# emg.net
KiCad netlist of a schematic drawn in EAGLE
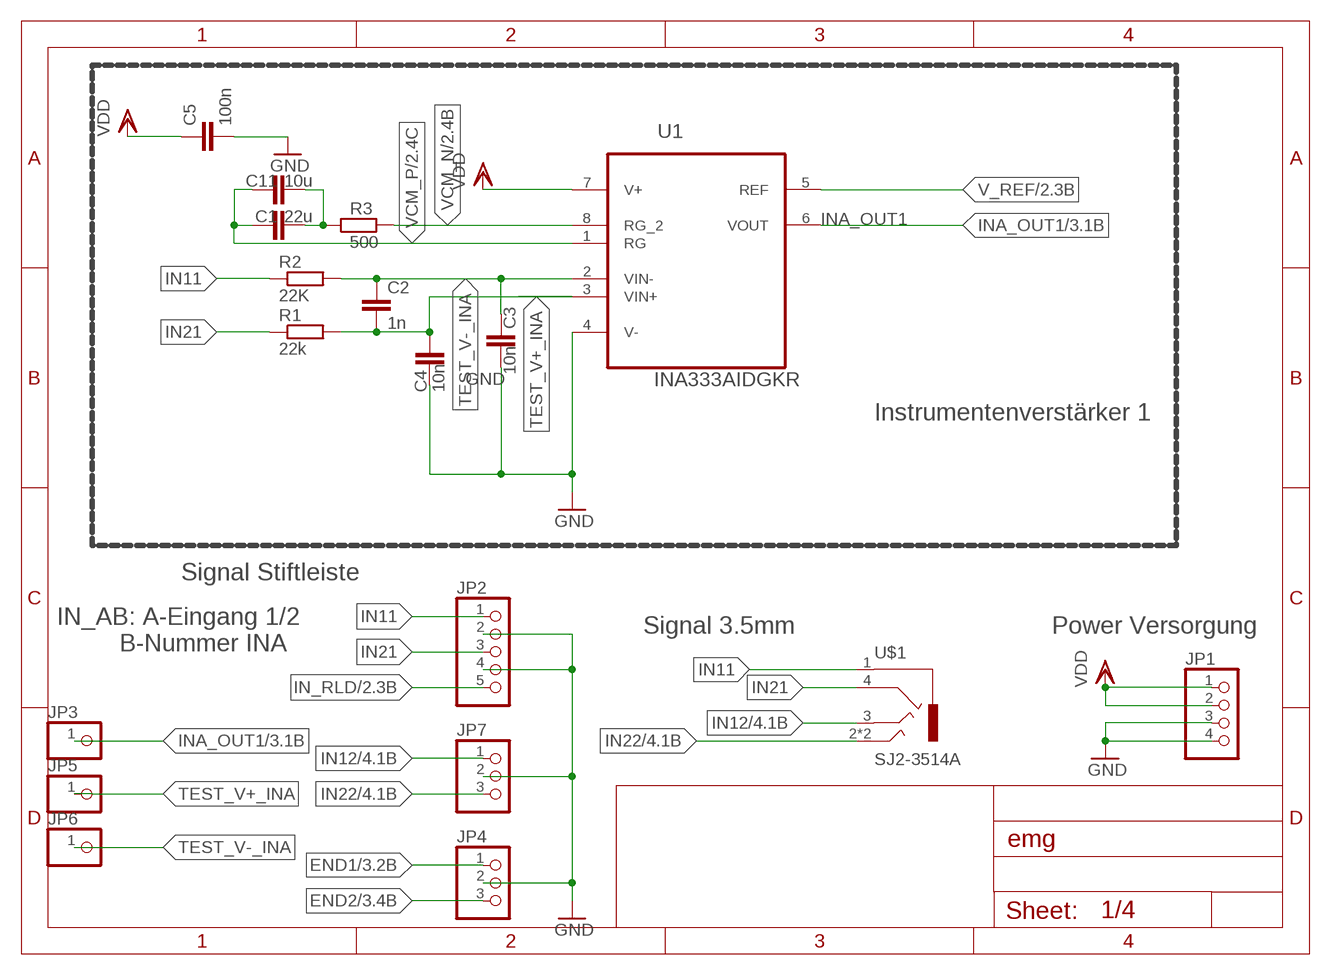
[diagram p0: schematic, sheet 1]
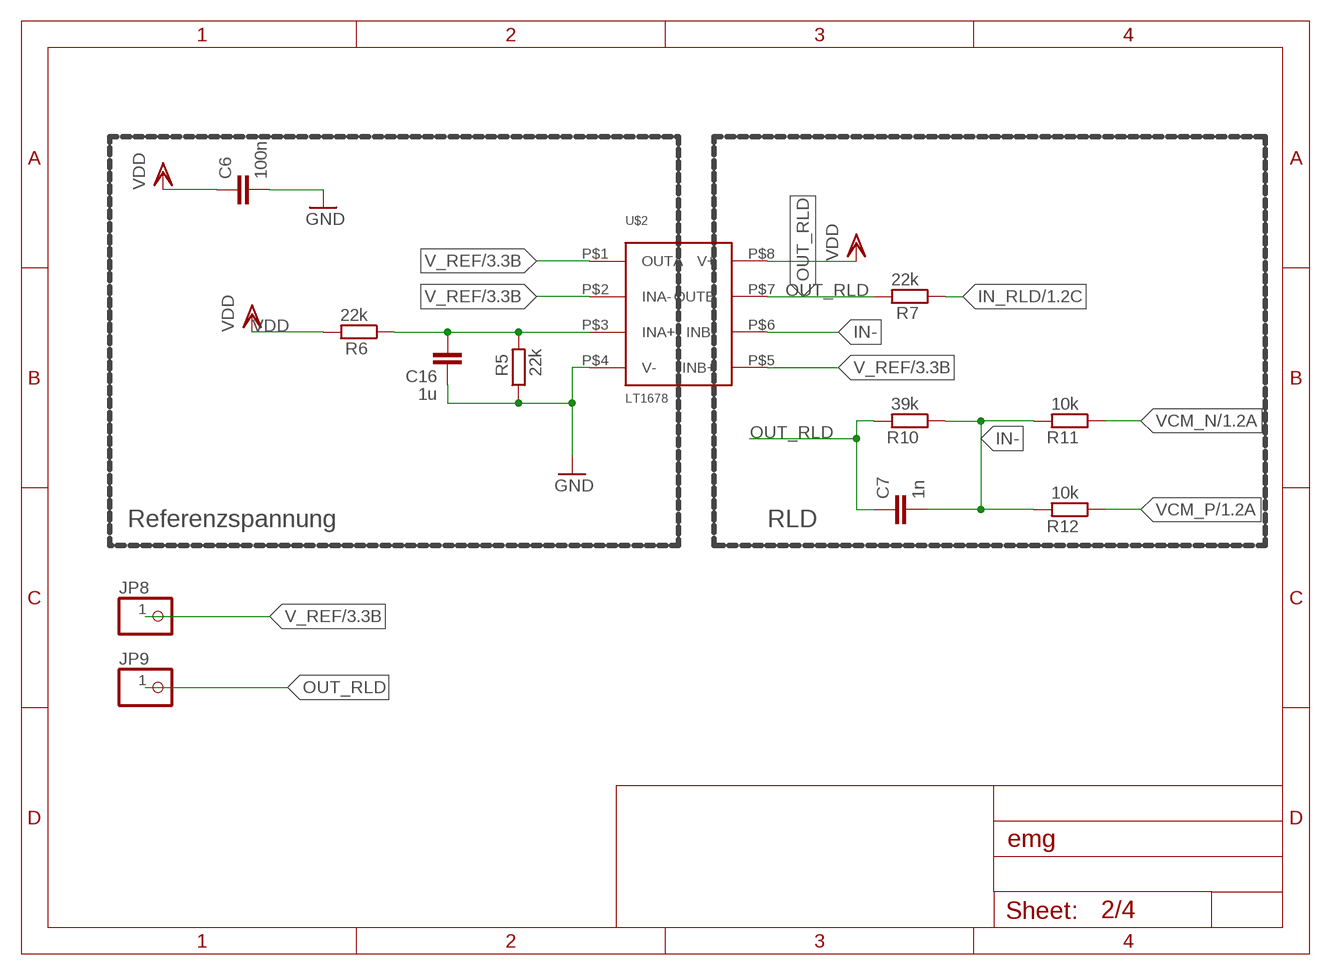
[diagram p1: schematic, sheet 2]
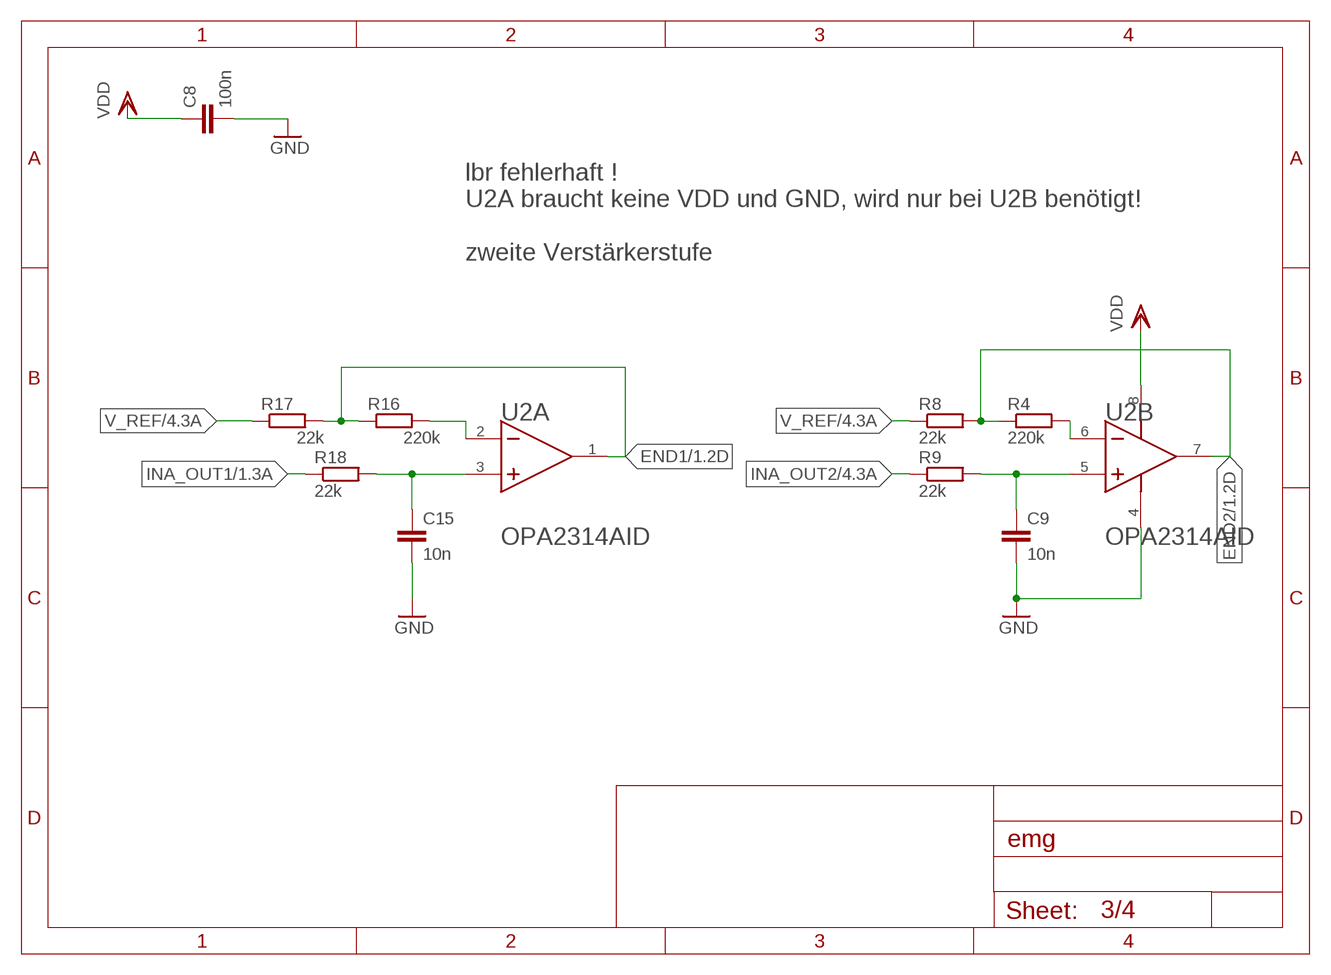
[diagram p2: schematic, sheet 3]
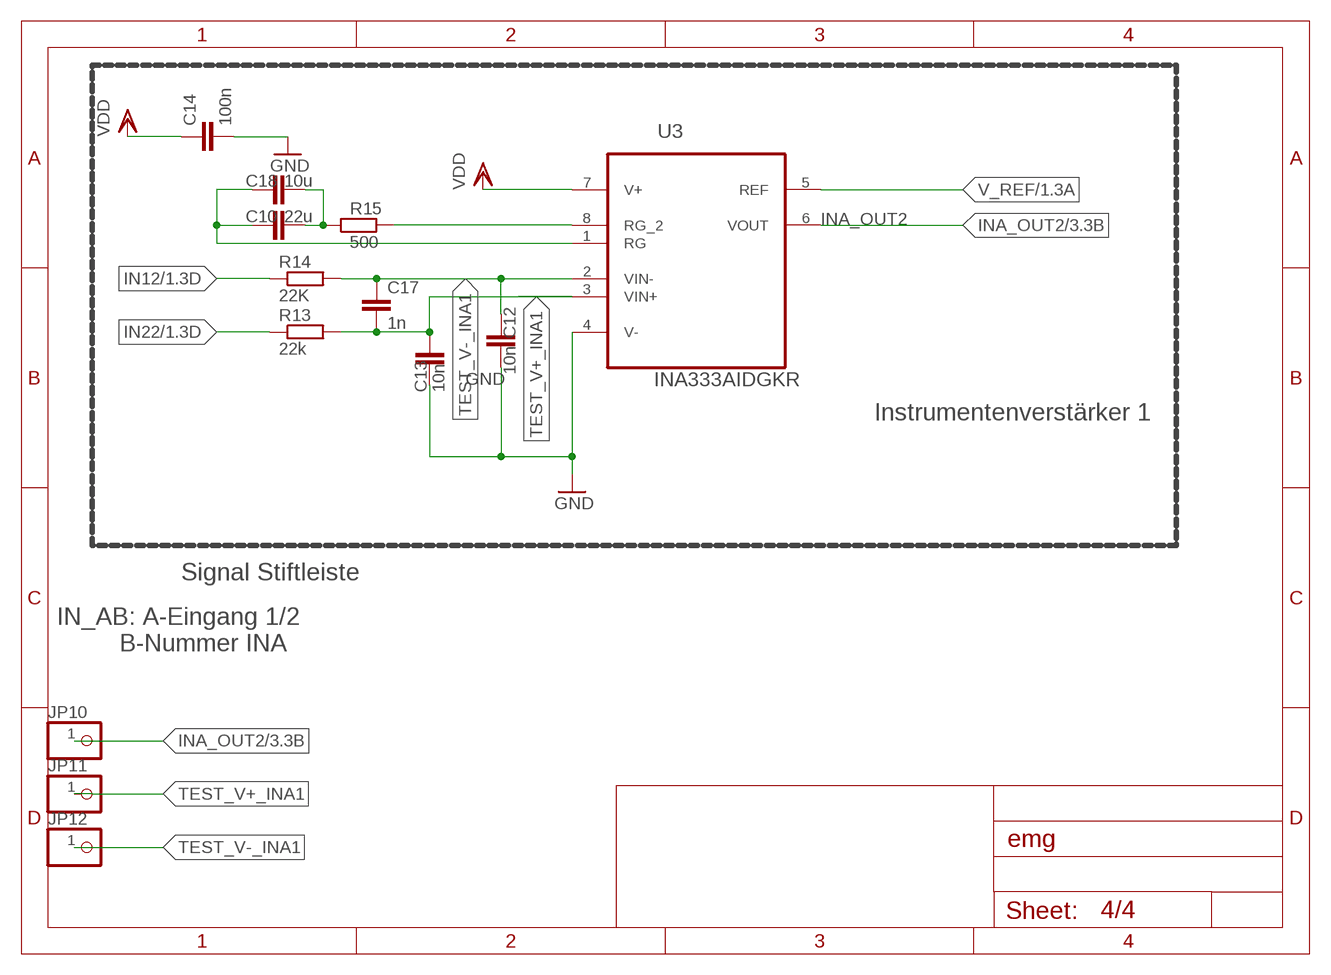
[diagram p3: schematic, sheet 4]

(export (version "E")
  (design (tool "Eeschema 10.0.6"))
  (components
    (comp (ref "C6")
      (value "100n")
      (footprint "eagle-import:C0805")
      (libsource (lib "eagle-import") (part "C-EUC0805"))
    )
    (comp (ref "C7")
      (value "1n")
      (footprint "eagle-import:C0805")
      (libsource (lib "eagle-import") (part "C-EUC0805"))
    )
    (comp (ref "C16")
      (value "1u")
      (footprint "eagle-import:C0805")
      (libsource (lib "eagle-import") (part "C-EUC0805"))
    )
    (comp (ref "JP8")
      (value "PINHD-1X1")
      (footprint "eagle-import:1X01")
      (libsource (lib "eagle-import") (part "PINHD-1X1"))
    )
    (comp (ref "JP9")
      (value "PINHD-1X1")
      (footprint "eagle-import:1X01")
      (libsource (lib "eagle-import") (part "PINHD-1X1"))
    )
    (comp (ref "R5")
      (value "22k")
      (footprint "eagle-import:R0805")
      (libsource (lib "eagle-import") (part "R-EU_R0805"))
    )
    (comp (ref "R6")
      (value "22k")
      (footprint "eagle-import:R0805")
      (libsource (lib "eagle-import") (part "R-EU_R0805"))
    )
    (comp (ref "R7")
      (value "22k")
      (footprint "eagle-import:R0805")
      (libsource (lib "eagle-import") (part "R-EU_R0805"))
    )
    (comp (ref "R10")
      (value "39k")
      (footprint "eagle-import:R0805")
      (libsource (lib "eagle-import") (part "R-EU_R0805"))
    )
    (comp (ref "R11")
      (value "10k")
      (footprint "eagle-import:R0805")
      (libsource (lib "eagle-import") (part "R-EU_R0805"))
    )
    (comp (ref "R12")
      (value "10k")
      (footprint "eagle-import:R0805")
      (libsource (lib "eagle-import") (part "R-EU_R0805"))
    )
    (comp (ref "U$2")
      (value "LT1678")
      (footprint "eagle-import:S8")
      (libsource (lib "eagle-import") (part "LT1678"))
    )
    (comp (ref "C8")
      (value "100n")
      (footprint "eagle-import:C0805")
      (libsource (lib "eagle-import") (part "C-EUC0805"))
    )
    (comp (ref "C9")
      (value "10n")
      (footprint "eagle-import:C0805")
      (libsource (lib "eagle-import") (part "C-EUC0805"))
    )
    (comp (ref "C15")
      (value "10n")
      (footprint "eagle-import:C0805")
      (libsource (lib "eagle-import") (part "C-EUC0805"))
    )
    (comp (ref "R4")
      (value "220k")
      (footprint "eagle-import:R0805")
      (libsource (lib "eagle-import") (part "R-EU_R0805"))
    )
    (comp (ref "R8")
      (value "22k")
      (footprint "eagle-import:R0805")
      (libsource (lib "eagle-import") (part "R-EU_R0805"))
    )
    (comp (ref "R9")
      (value "22k")
      (footprint "eagle-import:R0805")
      (libsource (lib "eagle-import") (part "R-EU_R0805"))
    )
    (comp (ref "R16")
      (value "220k")
      (footprint "eagle-import:R0805")
      (libsource (lib "eagle-import") (part "R-EU_R0805"))
    )
    (comp (ref "R17")
      (value "22k")
      (footprint "eagle-import:R0805")
      (libsource (lib "eagle-import") (part "R-EU_R0805"))
    )
    (comp (ref "R18")
      (value "22k")
      (footprint "eagle-import:R0805")
      (libsource (lib "eagle-import") (part "R-EU_R0805"))
    )
    (comp (ref "U2")
      (value "TEXAS_INSTRUMENTS_OPA2314AIDTEXAS_INSTRUMENTS_OPA2314AID_0_0")
      (footprint "eagle-import:TEXAS_INSTRUMENTS_OPA2314AID_0")
      (fields (field (name "MF") "Texas Instruments") (field (name "MPN") "OPA2314AID"))
      (libsource (lib "eagle-import") (part "TEXAS_INSTRUMENTS_OPA2314AIDTEXAS_INSTRUMENTS_OPA2314AID_0_0"))
    )
    (comp (ref "C10")
      (value "22u")
      (footprint "eagle-import:C0805")
      (libsource (lib "eagle-import") (part "C-EUC0805"))
    )
    (comp (ref "C12")
      (value "10n")
      (footprint "eagle-import:C0805")
      (libsource (lib "eagle-import") (part "C-EUC0805"))
    )
    (comp (ref "C13")
      (value "10n")
      (footprint "eagle-import:C0805")
      (libsource (lib "eagle-import") (part "C-EUC0805"))
    )
    (comp (ref "C14")
      (value "100n")
      (footprint "eagle-import:C0805")
      (libsource (lib "eagle-import") (part "C-EUC0805"))
    )
    (comp (ref "C17")
      (value "1n")
      (footprint "eagle-import:C0805")
      (libsource (lib "eagle-import") (part "C-EUC0805"))
    )
    (comp (ref "C18")
      (value "10u")
      (footprint "eagle-import:C0805")
      (libsource (lib "eagle-import") (part "C-EUC0805"))
    )
    (comp (ref "JP10")
      (value "PINHD-1X1")
      (footprint "eagle-import:1X01")
      (libsource (lib "eagle-import") (part "PINHD-1X1"))
    )
    (comp (ref "JP11")
      (value "PINHD-1X1")
      (footprint "eagle-import:1X01")
      (libsource (lib "eagle-import") (part "PINHD-1X1"))
    )
    (comp (ref "JP12")
      (value "PINHD-1X1")
      (footprint "eagle-import:1X01")
      (libsource (lib "eagle-import") (part "PINHD-1X1"))
    )
    (comp (ref "R13")
      (value "22k")
      (footprint "eagle-import:R0805")
      (libsource (lib "eagle-import") (part "R-EU_R0805"))
    )
    (comp (ref "R14")
      (value "22K")
      (footprint "eagle-import:R0805")
      (libsource (lib "eagle-import") (part "R-EU_R0805"))
    )
    (comp (ref "R15")
      (value "500")
      (footprint "eagle-import:R0805")
      (libsource (lib "eagle-import") (part "R-EU_R0805"))
    )
    (comp (ref "U3")
      (value "INA333AIDGKR")
      (footprint "eagle-import:SOP65P490X110-8N")
      (libsource (lib "eagle-import") (part "INA333AIDGKR"))
    )
    (comp (ref "C1")
      (value "22u")
      (footprint "eagle-import:C0805")
      (libsource (lib "eagle-import") (part "C-EUC0805"))
    )
    (comp (ref "C2")
      (value "1n")
      (footprint "eagle-import:C0805")
      (libsource (lib "eagle-import") (part "C-EUC0805"))
    )
    (comp (ref "C3")
      (value "10n")
      (footprint "eagle-import:C0805")
      (libsource (lib "eagle-import") (part "C-EUC0805"))
    )
    (comp (ref "C4")
      (value "10n")
      (footprint "eagle-import:C0805")
      (libsource (lib "eagle-import") (part "C-EUC0805"))
    )
    (comp (ref "C5")
      (value "100n")
      (footprint "eagle-import:C0805")
      (libsource (lib "eagle-import") (part "C-EUC0805"))
    )
    (comp (ref "C11")
      (value "10u")
      (footprint "eagle-import:C0805")
      (libsource (lib "eagle-import") (part "C-EUC0805"))
    )
    (comp (ref "JP1")
      (value "PINHD-1X4")
      (footprint "eagle-import:1X04")
      (libsource (lib "eagle-import") (part "PINHD-1X4"))
    )
    (comp (ref "JP2")
      (value "PINHD-1X5")
      (footprint "eagle-import:1X05")
      (libsource (lib "eagle-import") (part "PINHD-1X5"))
    )
    (comp (ref "JP3")
      (value "PINHD-1X1")
      (footprint "eagle-import:1X01")
      (libsource (lib "eagle-import") (part "PINHD-1X1"))
    )
    (comp (ref "JP4")
      (value "PINHD-1X3")
      (footprint "eagle-import:1X03")
      (libsource (lib "eagle-import") (part "PINHD-1X3"))
    )
    (comp (ref "JP5")
      (value "PINHD-1X1")
      (footprint "eagle-import:1X01")
      (libsource (lib "eagle-import") (part "PINHD-1X1"))
    )
    (comp (ref "JP6")
      (value "PINHD-1X1")
      (footprint "eagle-import:1X01")
      (libsource (lib "eagle-import") (part "PINHD-1X1"))
    )
    (comp (ref "JP7")
      (value "PINHD-1X3")
      (footprint "eagle-import:1X03")
      (libsource (lib "eagle-import") (part "PINHD-1X3"))
    )
    (comp (ref "R1")
      (value "22k")
      (footprint "eagle-import:R0805")
      (libsource (lib "eagle-import") (part "R-EU_R0805"))
    )
    (comp (ref "R2")
      (value "22K")
      (footprint "eagle-import:R0805")
      (libsource (lib "eagle-import") (part "R-EU_R0805"))
    )
    (comp (ref "R3")
      (value "500")
      (footprint "eagle-import:R0805")
      (libsource (lib "eagle-import") (part "R-EU_R0805"))
    )
    (comp (ref "U$1")
      (value "SJ2-3514A")
      (footprint "eagle-import:USR_SJ2-4514A")
      (libsource (lib "eagle-import") (part "SJ2-3514A"))
    )
    (comp (ref "U1")
      (value "INA333AIDGKR")
      (footprint "eagle-import:SOP65P490X110-8N")
      (libsource (lib "eagle-import") (part "INA333AIDGKR"))
    )
  )
  (nets
    (net (code "1") (name "END1") (class "Default")
      (node (ref "JP4") (pin "1") (pinfunction "1_1") (pintype "passive"))
      (node (ref "R16") (pin "1") (pinfunction "1_1") (pintype "passive"))
      (node (ref "R17") (pin "2") (pinfunction "2_2") (pintype "passive"))
      (node (ref "U2") (pin "1") (pinfunction "OUT_A_1") (pintype "output"))
    )
    (net (code "2") (name "END2") (class "Default")
      (node (ref "JP4") (pin "3") (pinfunction "3_3") (pintype "passive"))
      (node (ref "R4") (pin "1") (pinfunction "1_1") (pintype "passive"))
      (node (ref "R8") (pin "2") (pinfunction "2_2") (pintype "passive"))
      (node (ref "U2") (pin "7") (pinfunction "OUT_B_7") (pintype "output"))
    )
    (net (code "3") (name "GND") (class "Default")
      (node (ref "C12") (pin "2") (pinfunction "2_2") (pintype "passive"))
      (node (ref "C13") (pin "2") (pinfunction "2_2") (pintype "passive"))
      (node (ref "C14") (pin "2") (pinfunction "2_2") (pintype "passive"))
      (node (ref "C15") (pin "2") (pinfunction "2_2") (pintype "passive"))
      (node (ref "C16") (pin "1") (pinfunction "1_1") (pintype "passive"))
      (node (ref "C3") (pin "2") (pinfunction "2_2") (pintype "passive"))
      (node (ref "C4") (pin "2") (pinfunction "2_2") (pintype "passive"))
      (node (ref "C5") (pin "2") (pinfunction "2_2") (pintype "passive"))
      (node (ref "C6") (pin "2") (pinfunction "2_2") (pintype "passive"))
      (node (ref "C8") (pin "2") (pinfunction "2_2") (pintype "passive"))
      (node (ref "C9") (pin "2") (pinfunction "2_2") (pintype "passive"))
      (node (ref "JP1") (pin "3") (pinfunction "3_3") (pintype "passive"))
      (node (ref "JP1") (pin "4") (pinfunction "4_4") (pintype "passive"))
      (node (ref "JP2") (pin "2") (pinfunction "2_2") (pintype "passive"))
      (node (ref "JP2") (pin "4") (pinfunction "4_4") (pintype "passive"))
      (node (ref "JP4") (pin "2") (pinfunction "2_2") (pintype "passive"))
      (node (ref "JP7") (pin "2") (pinfunction "2_2") (pintype "passive"))
      (node (ref "R5") (pin "1") (pinfunction "1_1") (pintype "passive"))
      (node (ref "U$2") (pin "P$4") (pinfunction "V-_P$4") (pintype "power_in"))
      (node (ref "U1") (pin "4") (pinfunction "V-_4") (pintype "power_in"))
      (node (ref "U2") (pin "4") (pinfunction "V-_4") (pintype "power_in"))
      (node (ref "U3") (pin "4") (pinfunction "V-_4") (pintype "power_in"))
    )
    (net (code "4") (name "IN-") (class "Default")
      (node (ref "C7") (pin "2") (pinfunction "2_2") (pintype "passive"))
      (node (ref "R10") (pin "1") (pinfunction "1_1") (pintype "passive"))
      (node (ref "R11") (pin "2") (pinfunction "2_2") (pintype "passive"))
      (node (ref "R12") (pin "2") (pinfunction "2_2") (pintype "passive"))
      (node (ref "U$2") (pin "P$6") (pinfunction "INB-_P$6") (pintype "input"))
    )
    (net (code "5") (name "IN11") (class "Default")
      (node (ref "JP2") (pin "1") (pinfunction "1_1") (pintype "passive"))
      (node (ref "R2") (pin "1") (pinfunction "1_1") (pintype "passive"))
      (node (ref "U$1") (pin "1") (pinfunction "1_1") (pintype "passive"))
    )
    (net (code "6") (name "IN12") (class "Default")
      (node (ref "JP7") (pin "1") (pinfunction "1_1") (pintype "passive"))
      (node (ref "R14") (pin "1") (pinfunction "1_1") (pintype "passive"))
      (node (ref "U$1") (pin "3") (pinfunction "3_3") (pintype "passive"))
    )
    (net (code "7") (name "IN21") (class "Default")
      (node (ref "JP2") (pin "3") (pinfunction "3_3") (pintype "passive"))
      (node (ref "R1") (pin "1") (pinfunction "1_1") (pintype "passive"))
      (node (ref "U$1") (pin "4") (pinfunction "4_4") (pintype "passive"))
    )
    (net (code "8") (name "IN22") (class "Default")
      (node (ref "JP7") (pin "3") (pinfunction "3_3") (pintype "passive"))
      (node (ref "R13") (pin "1") (pinfunction "1_1") (pintype "passive"))
      (node (ref "U$1") (pin "2") (pinfunction "2_2") (pintype "passive"))
      (node (ref "U$1") (pin "2_2") (pinfunction "2_2_2") (pintype "passive"))
    )
    (net (code "9") (name "INA_OUT1") (class "Default")
      (node (ref "JP3") (pin "1") (pinfunction "1_1") (pintype "passive"))
      (node (ref "R18") (pin "1") (pinfunction "1_1") (pintype "passive"))
      (node (ref "U1") (pin "6") (pinfunction "VOUT_6") (pintype "output"))
    )
    (net (code "10") (name "INA_OUT2") (class "Default")
      (node (ref "JP10") (pin "1") (pinfunction "1_1") (pintype "passive"))
      (node (ref "R9") (pin "1") (pinfunction "1_1") (pintype "passive"))
      (node (ref "U3") (pin "6") (pinfunction "VOUT_6") (pintype "output"))
    )
    (net (code "11") (name "IN_RLD") (class "Default")
      (node (ref "JP2") (pin "5") (pinfunction "5_5") (pintype "passive"))
      (node (ref "R7") (pin "1") (pinfunction "1_1") (pintype "passive"))
    )
    (net (code "12") (name "Net-(C1-Pad2)") (class "Default")
      (node (ref "C1") (pin "2") (pinfunction "2_2") (pintype "passive"))
      (node (ref "C11") (pin "2") (pinfunction "2_2") (pintype "passive"))
      (node (ref "R3") (pin "1") (pinfunction "1_1") (pintype "passive"))
    )
    (net (code "13") (name "Net-(C10-Pad2)") (class "Default")
      (node (ref "C10") (pin "2") (pinfunction "2_2") (pintype "passive"))
      (node (ref "C18") (pin "2") (pinfunction "2_2") (pintype "passive"))
      (node (ref "R15") (pin "1") (pinfunction "1_1") (pintype "passive"))
    )
    (net (code "14") (name "Net-(U$2-INA+)") (class "Default")
      (node (ref "C16") (pin "2") (pinfunction "2_2") (pintype "passive"))
      (node (ref "R5") (pin "2") (pinfunction "2_2") (pintype "passive"))
      (node (ref "R6") (pin "1") (pinfunction "1_1") (pintype "passive"))
      (node (ref "U$2") (pin "P$3") (pinfunction "INA+_P$3") (pintype "input"))
    )
    (net (code "15") (name "Net-(U2A-IN_A+)") (class "Default")
      (node (ref "C15") (pin "1") (pinfunction "1_1") (pintype "passive"))
      (node (ref "R18") (pin "2") (pinfunction "2_2") (pintype "passive"))
      (node (ref "U2") (pin "3") (pinfunction "IN_A+_3") (pintype "input"))
    )
    (net (code "16") (name "Net-(U2A-IN_A-)") (class "Default")
      (node (ref "R16") (pin "2") (pinfunction "2_2") (pintype "passive"))
      (node (ref "U2") (pin "2") (pinfunction "IN_A-_2") (pintype "input"))
    )
    (net (code "17") (name "Net-(U2B-IN_B+)") (class "Default")
      (node (ref "C9") (pin "1") (pinfunction "1_1") (pintype "passive"))
      (node (ref "R9") (pin "2") (pinfunction "2_2") (pintype "passive"))
      (node (ref "U2") (pin "5") (pinfunction "IN_B+_5") (pintype "input"))
    )
    (net (code "18") (name "Net-(U2B-IN_B-)") (class "Default")
      (node (ref "R4") (pin "2") (pinfunction "2_2") (pintype "passive"))
      (node (ref "U2") (pin "6") (pinfunction "IN_B-_6") (pintype "input"))
    )
    (net (code "19") (name "Net-(U3-RG)") (class "Default")
      (node (ref "C10") (pin "1") (pinfunction "1_1") (pintype "passive"))
      (node (ref "C18") (pin "1") (pinfunction "1_1") (pintype "passive"))
      (node (ref "U3") (pin "1") (pinfunction "RG_1") (pintype "input"))
    )
    (net (code "20") (name "Net-(U3-RG_2)") (class "Default")
      (node (ref "R15") (pin "2") (pinfunction "2_2") (pintype "passive"))
      (node (ref "U3") (pin "8") (pinfunction "RG_2_8") (pintype "input"))
    )
    (net (code "21") (name "OUT_RLD") (class "Default")
      (node (ref "C7") (pin "1") (pinfunction "1_1") (pintype "passive"))
      (node (ref "JP9") (pin "1") (pinfunction "1_1") (pintype "passive"))
      (node (ref "R10") (pin "2") (pinfunction "2_2") (pintype "passive"))
      (node (ref "R7") (pin "2") (pinfunction "2_2") (pintype "passive"))
      (node (ref "U$2") (pin "P$7") (pinfunction "OUTB_P$7") (pintype "output"))
    )
    (net (code "22") (name "TEST_V+_INA") (class "Default")
      (node (ref "C2") (pin "2") (pinfunction "2_2") (pintype "passive"))
      (node (ref "C4") (pin "1") (pinfunction "1_1") (pintype "passive"))
      (node (ref "JP5") (pin "1") (pinfunction "1_1") (pintype "passive"))
      (node (ref "R1") (pin "2") (pinfunction "2_2") (pintype "passive"))
      (node (ref "U1") (pin "3") (pinfunction "VIN+_3") (pintype "input"))
    )
    (net (code "23") (name "TEST_V+_INA1") (class "Default")
      (node (ref "C13") (pin "1") (pinfunction "1_1") (pintype "passive"))
      (node (ref "C17") (pin "2") (pinfunction "2_2") (pintype "passive"))
      (node (ref "JP11") (pin "1") (pinfunction "1_1") (pintype "passive"))
      (node (ref "R13") (pin "2") (pinfunction "2_2") (pintype "passive"))
      (node (ref "U3") (pin "3") (pinfunction "VIN+_3") (pintype "input"))
    )
    (net (code "24") (name "TEST_V-_INA") (class "Default")
      (node (ref "C2") (pin "1") (pinfunction "1_1") (pintype "passive"))
      (node (ref "C3") (pin "1") (pinfunction "1_1") (pintype "passive"))
      (node (ref "JP6") (pin "1") (pinfunction "1_1") (pintype "passive"))
      (node (ref "R2") (pin "2") (pinfunction "2_2") (pintype "passive"))
      (node (ref "U1") (pin "2") (pinfunction "VIN-_2") (pintype "input"))
    )
    (net (code "25") (name "TEST_V-_INA1") (class "Default")
      (node (ref "C12") (pin "1") (pinfunction "1_1") (pintype "passive"))
      (node (ref "C17") (pin "1") (pinfunction "1_1") (pintype "passive"))
      (node (ref "JP12") (pin "1") (pinfunction "1_1") (pintype "passive"))
      (node (ref "R14") (pin "2") (pinfunction "2_2") (pintype "passive"))
      (node (ref "U3") (pin "2") (pinfunction "VIN-_2") (pintype "input"))
    )
    (net (code "26") (name "VCM_N") (class "Default")
      (node (ref "R11") (pin "1") (pinfunction "1_1") (pintype "passive"))
      (node (ref "R3") (pin "2") (pinfunction "2_2") (pintype "passive"))
      (node (ref "U1") (pin "8") (pinfunction "RG_2_8") (pintype "input"))
    )
    (net (code "27") (name "VCM_P") (class "Default")
      (node (ref "C1") (pin "1") (pinfunction "1_1") (pintype "passive"))
      (node (ref "C11") (pin "1") (pinfunction "1_1") (pintype "passive"))
      (node (ref "R12") (pin "1") (pinfunction "1_1") (pintype "passive"))
      (node (ref "U1") (pin "1") (pinfunction "RG_1") (pintype "input"))
    )
    (net (code "28") (name "VDD") (class "Default")
      (node (ref "C14") (pin "1") (pinfunction "1_1") (pintype "passive"))
      (node (ref "C5") (pin "1") (pinfunction "1_1") (pintype "passive"))
      (node (ref "C6") (pin "1") (pinfunction "1_1") (pintype "passive"))
      (node (ref "C8") (pin "1") (pinfunction "1_1") (pintype "passive"))
      (node (ref "JP1") (pin "1") (pinfunction "1_1") (pintype "passive"))
      (node (ref "JP1") (pin "2") (pinfunction "2_2") (pintype "passive"))
      (node (ref "R6") (pin "2") (pinfunction "2_2") (pintype "passive"))
      (node (ref "U$2") (pin "P$8") (pinfunction "V+_P$8") (pintype "power_in"))
      (node (ref "U1") (pin "7") (pinfunction "V+_7") (pintype "power_in"))
      (node (ref "U2") (pin "8") (pinfunction "V+_8") (pintype "power_in"))
      (node (ref "U3") (pin "7") (pinfunction "V+_7") (pintype "power_in"))
    )
    (net (code "29") (name "V_REF") (class "Default")
      (node (ref "JP8") (pin "1") (pinfunction "1_1") (pintype "passive"))
      (node (ref "R17") (pin "1") (pinfunction "1_1") (pintype "passive"))
      (node (ref "R8") (pin "1") (pinfunction "1_1") (pintype "passive"))
      (node (ref "U$2") (pin "P$1") (pinfunction "OUTA_P$1") (pintype "output"))
      (node (ref "U$2") (pin "P$2") (pinfunction "INA-_P$2") (pintype "input"))
      (node (ref "U$2") (pin "P$5") (pinfunction "INB+_P$5") (pintype "input"))
      (node (ref "U1") (pin "5") (pinfunction "REF_5") (pintype "output"))
      (node (ref "U3") (pin "5") (pinfunction "REF_5") (pintype "output"))
    )
  )
)
